# imu_3_yz.net
KiCad netlist of a schematic drawn in EAGLE
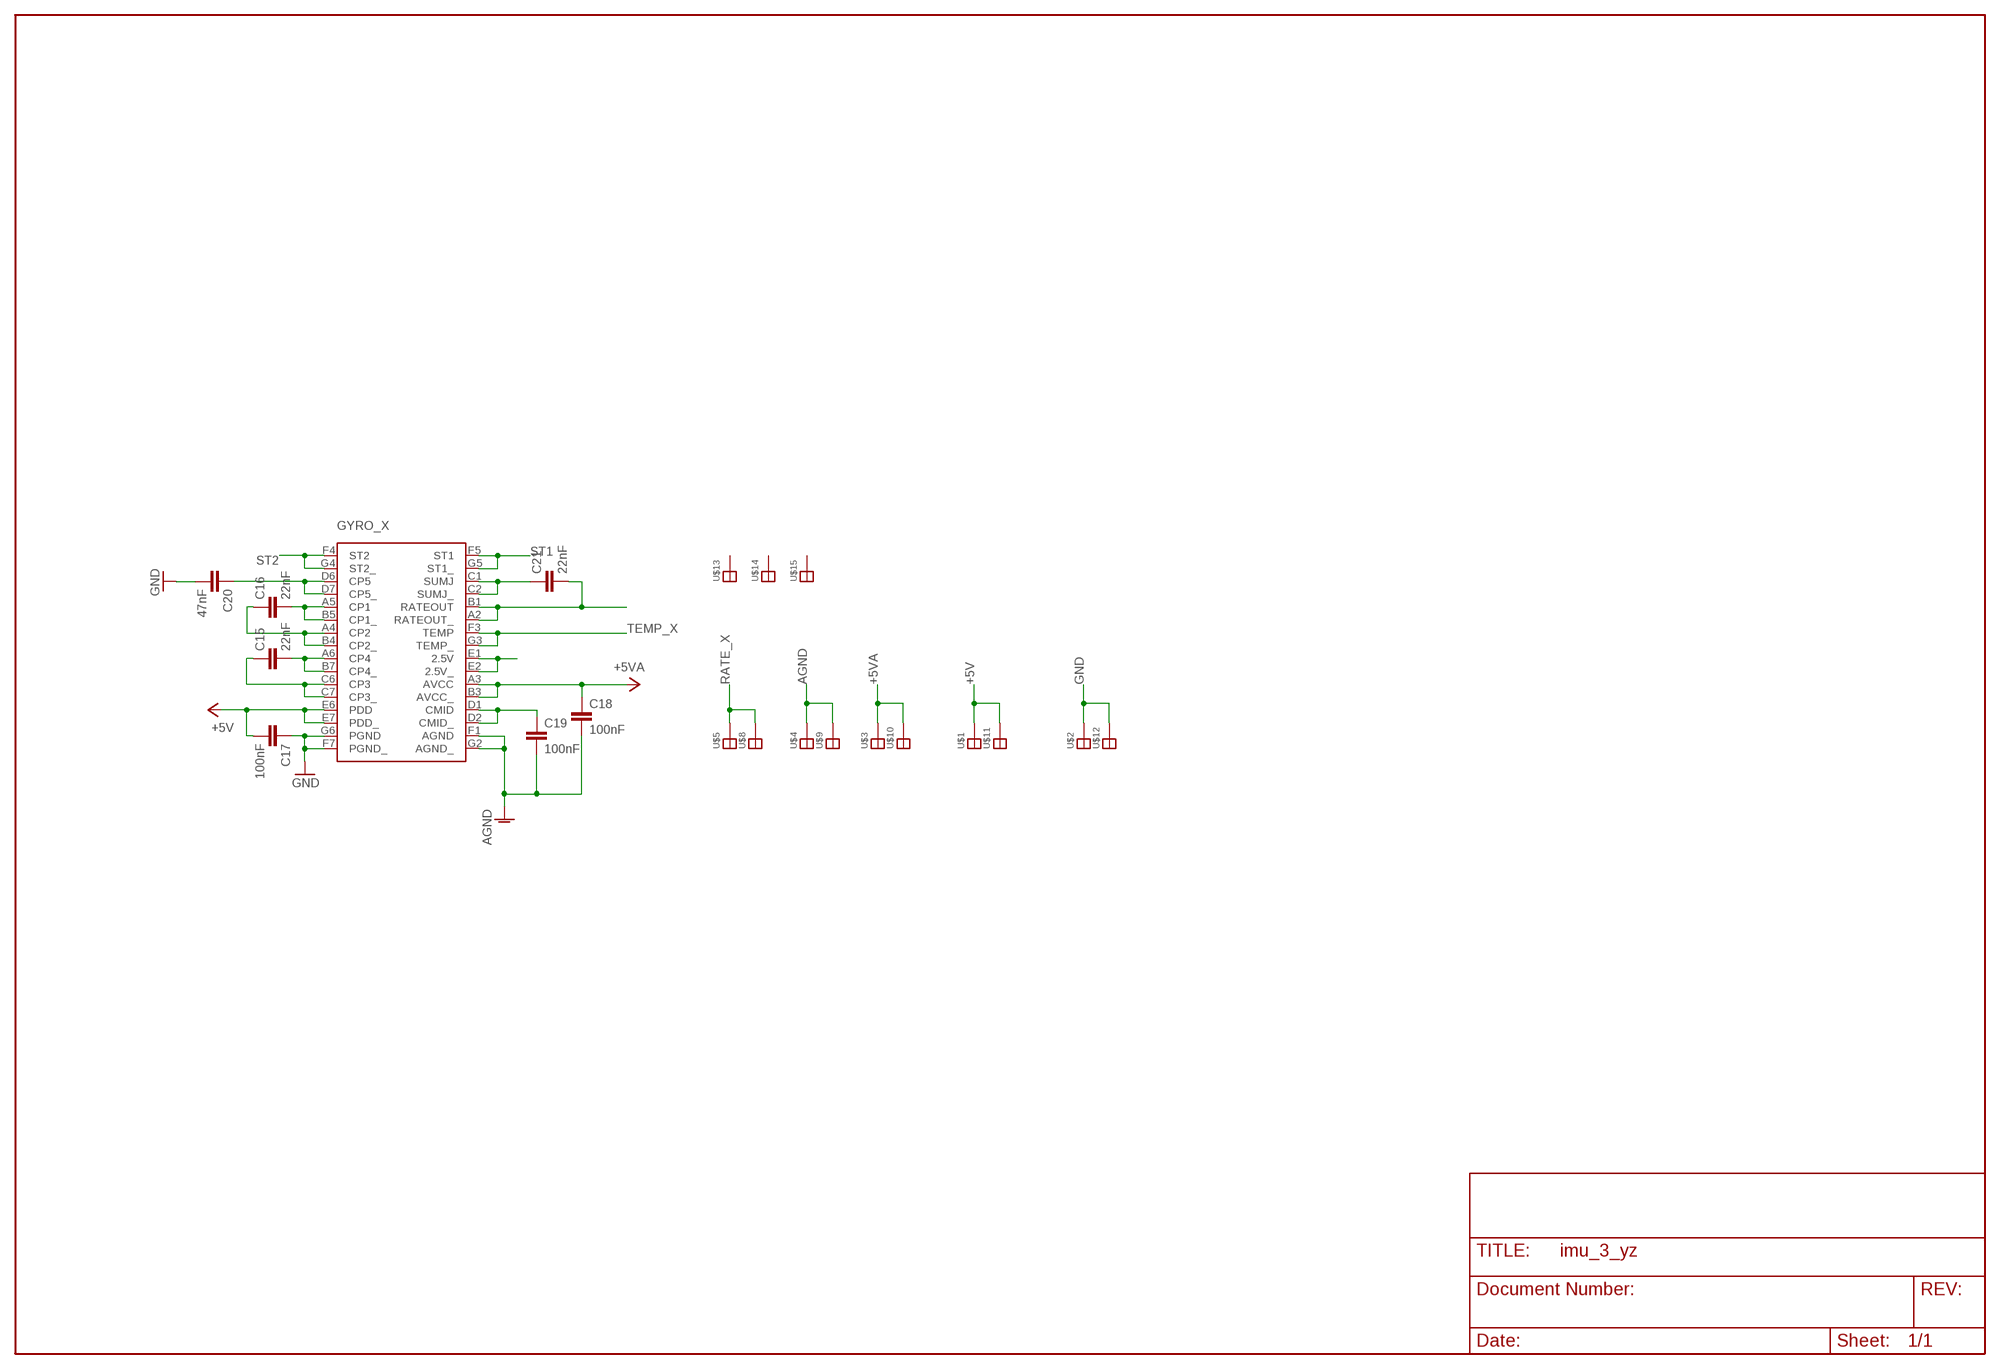
[diagram p0: schematic, sheet 1]

(export (version "E")
  (design (tool "Eeschema 10.0.6"))
  (components
    (comp (ref "C15")
      (value "22nF")
      (footprint "eagle-import:C0402K")
      (libsource (lib "eagle-import") (part "C-EUC0402K"))
    )
    (comp (ref "C16")
      (value "22nF")
      (footprint "eagle-import:C0402K")
      (libsource (lib "eagle-import") (part "C-EUC0402K"))
    )
    (comp (ref "C17")
      (value "100nF")
      (footprint "eagle-import:C0402K")
      (libsource (lib "eagle-import") (part "C-EUC0402K"))
    )
    (comp (ref "C18")
      (value "100nF")
      (footprint "eagle-import:C0402K")
      (libsource (lib "eagle-import") (part "C-EUC0402K"))
    )
    (comp (ref "C19")
      (value "100nF")
      (footprint "eagle-import:C0402K")
      (libsource (lib "eagle-import") (part "C-EUC0402K"))
    )
    (comp (ref "C20")
      (value "47nF")
      (footprint "eagle-import:C0402K")
      (libsource (lib "eagle-import") (part "C-EUC0402K"))
    )
    (comp (ref "C21")
      (value "22nF")
      (footprint "eagle-import:C0402K")
      (libsource (lib "eagle-import") (part "C-EUC0402K"))
    )
    (comp (ref "GYRO_X")
      (value "ADXR")
      (footprint "eagle-import:BC-32")
      (libsource (lib "eagle-import") (part "ADXR"))
    )
    (comp (ref "U$1")
      (value "SOLDER_PAD")
      (footprint "eagle-import:SOLDER_PAD")
      (libsource (lib "eagle-import") (part "SOLDER_PAD"))
    )
    (comp (ref "U$2")
      (value "SOLDER_PAD")
      (footprint "eagle-import:SOLDER_PAD")
      (libsource (lib "eagle-import") (part "SOLDER_PAD"))
    )
    (comp (ref "U$3")
      (value "SOLDER_PAD")
      (footprint "eagle-import:SOLDER_PAD")
      (libsource (lib "eagle-import") (part "SOLDER_PAD"))
    )
    (comp (ref "U$4")
      (value "SOLDER_PAD")
      (footprint "eagle-import:SOLDER_PAD")
      (libsource (lib "eagle-import") (part "SOLDER_PAD"))
    )
    (comp (ref "U$5")
      (value "SOLDER_PAD")
      (footprint "eagle-import:SOLDER_PAD")
      (libsource (lib "eagle-import") (part "SOLDER_PAD"))
    )
    (comp (ref "U$8")
      (value "SOLDER_PAD")
      (footprint "eagle-import:SOLDER_PAD")
      (libsource (lib "eagle-import") (part "SOLDER_PAD"))
    )
    (comp (ref "U$9")
      (value "SOLDER_PAD")
      (footprint "eagle-import:SOLDER_PAD")
      (libsource (lib "eagle-import") (part "SOLDER_PAD"))
    )
    (comp (ref "U$10")
      (value "SOLDER_PAD")
      (footprint "eagle-import:SOLDER_PAD")
      (libsource (lib "eagle-import") (part "SOLDER_PAD"))
    )
    (comp (ref "U$11")
      (value "SOLDER_PAD")
      (footprint "eagle-import:SOLDER_PAD")
      (libsource (lib "eagle-import") (part "SOLDER_PAD"))
    )
    (comp (ref "U$12")
      (value "SOLDER_PAD")
      (footprint "eagle-import:SOLDER_PAD")
      (libsource (lib "eagle-import") (part "SOLDER_PAD"))
    )
    (comp (ref "U$13")
      (value "SOLDER_PAD")
      (footprint "eagle-import:SOLDER_PAD")
      (libsource (lib "eagle-import") (part "SOLDER_PAD"))
    )
    (comp (ref "U$14")
      (value "SOLDER_PAD")
      (footprint "eagle-import:SOLDER_PAD")
      (libsource (lib "eagle-import") (part "SOLDER_PAD"))
    )
    (comp (ref "U$15")
      (value "SOLDER_PAD")
      (footprint "eagle-import:SOLDER_PAD")
      (libsource (lib "eagle-import") (part "SOLDER_PAD"))
    )
  )
  (nets
    (net (code "1") (name "+5V") (class "Default")
      (node (ref "C17") (pin "2") (pinfunction "2_2") (pintype "passive"))
      (node (ref "GYRO_X") (pin "E6") (pinfunction "PDD_E6") (pintype "bidirectional"))
      (node (ref "GYRO_X") (pin "E7") (pinfunction "PDD__E7") (pintype "bidirectional"))
      (node (ref "U$1") (pin "P$1") (pinfunction "P$1_P$1") (pintype "bidirectional"))
      (node (ref "U$11") (pin "P$1") (pinfunction "P$1_P$1") (pintype "bidirectional"))
    )
    (net (code "2") (name "+5VA") (class "Default")
      (node (ref "C18") (pin "1") (pinfunction "1_1") (pintype "passive"))
      (node (ref "GYRO_X") (pin "A3") (pinfunction "AVCC_A3") (pintype "bidirectional"))
      (node (ref "GYRO_X") (pin "B3") (pinfunction "AVCC__B3") (pintype "bidirectional"))
      (node (ref "U$10") (pin "P$1") (pinfunction "P$1_P$1") (pintype "bidirectional"))
      (node (ref "U$3") (pin "P$1") (pinfunction "P$1_P$1") (pintype "bidirectional"))
    )
    (net (code "3") (name "/RATE_X") (class "Default")
      (node (ref "C21") (pin "2") (pinfunction "2_2") (pintype "passive"))
      (node (ref "GYRO_X") (pin "A2") (pinfunction "RATEOUT__A2") (pintype "bidirectional"))
      (node (ref "GYRO_X") (pin "B1") (pinfunction "RATEOUT_B1") (pintype "bidirectional"))
      (node (ref "U$5") (pin "P$1") (pinfunction "P$1_P$1") (pintype "bidirectional"))
      (node (ref "U$8") (pin "P$1") (pinfunction "P$1_P$1") (pintype "bidirectional"))
    )
    (net (code "4") (name "/ST1") (class "Default")
      (node (ref "GYRO_X") (pin "F5") (pinfunction "ST1_F5") (pintype "bidirectional"))
      (node (ref "GYRO_X") (pin "G5") (pinfunction "ST1__G5") (pintype "bidirectional"))
    )
    (net (code "5") (name "/ST2") (class "Default")
      (node (ref "GYRO_X") (pin "F4") (pinfunction "ST2_F4") (pintype "bidirectional"))
      (node (ref "GYRO_X") (pin "G4") (pinfunction "ST2__G4") (pintype "bidirectional"))
    )
    (net (code "6") (name "/TEMP_X") (class "Default")
      (node (ref "GYRO_X") (pin "F3") (pinfunction "TEMP_F3") (pintype "bidirectional"))
      (node (ref "GYRO_X") (pin "G3") (pinfunction "TEMP__G3") (pintype "bidirectional"))
    )
    (net (code "7") (name "AGND") (class "Default")
      (node (ref "C18") (pin "2") (pinfunction "2_2") (pintype "passive"))
      (node (ref "C19") (pin "2") (pinfunction "2_2") (pintype "passive"))
      (node (ref "GYRO_X") (pin "F1") (pinfunction "AGND_F1") (pintype "bidirectional"))
      (node (ref "GYRO_X") (pin "G2") (pinfunction "AGND__G2") (pintype "bidirectional"))
      (node (ref "U$4") (pin "P$1") (pinfunction "P$1_P$1") (pintype "bidirectional"))
      (node (ref "U$9") (pin "P$1") (pinfunction "P$1_P$1") (pintype "bidirectional"))
    )
    (net (code "8") (name "GND") (class "Default")
      (node (ref "C17") (pin "1") (pinfunction "1_1") (pintype "passive"))
      (node (ref "C20") (pin "2") (pinfunction "2_2") (pintype "passive"))
      (node (ref "GYRO_X") (pin "F7") (pinfunction "PGND__F7") (pintype "bidirectional"))
      (node (ref "GYRO_X") (pin "G6") (pinfunction "PGND_G6") (pintype "bidirectional"))
      (node (ref "U$12") (pin "P$1") (pinfunction "P$1_P$1") (pintype "bidirectional"))
      (node (ref "U$2") (pin "P$1") (pinfunction "P$1_P$1") (pintype "bidirectional"))
    )
    (net (code "9") (name "Net-(GYRO_X-2.5V)") (class "Default")
      (node (ref "GYRO_X") (pin "E1") (pinfunction "2.5V_E1") (pintype "bidirectional"))
      (node (ref "GYRO_X") (pin "E2") (pinfunction "2.5V__E2") (pintype "bidirectional"))
    )
    (net (code "10") (name "Net-(GYRO_X-CMID)") (class "Default")
      (node (ref "C19") (pin "1") (pinfunction "1_1") (pintype "passive"))
      (node (ref "GYRO_X") (pin "D1") (pinfunction "CMID_D1") (pintype "bidirectional"))
      (node (ref "GYRO_X") (pin "D2") (pinfunction "CMID__D2") (pintype "bidirectional"))
    )
    (net (code "11") (name "Net-(GYRO_X-CP1)") (class "Default")
      (node (ref "C16") (pin "2") (pinfunction "2_2") (pintype "passive"))
      (node (ref "GYRO_X") (pin "A5") (pinfunction "CP1_A5") (pintype "bidirectional"))
      (node (ref "GYRO_X") (pin "B5") (pinfunction "CP1__B5") (pintype "bidirectional"))
    )
    (net (code "12") (name "Net-(GYRO_X-CP2)") (class "Default")
      (node (ref "C16") (pin "1") (pinfunction "1_1") (pintype "passive"))
      (node (ref "GYRO_X") (pin "A4") (pinfunction "CP2_A4") (pintype "bidirectional"))
      (node (ref "GYRO_X") (pin "B4") (pinfunction "CP2__B4") (pintype "bidirectional"))
    )
    (net (code "13") (name "Net-(GYRO_X-CP3)") (class "Default")
      (node (ref "C15") (pin "1") (pinfunction "1_1") (pintype "passive"))
      (node (ref "GYRO_X") (pin "C6") (pinfunction "CP3_C6") (pintype "bidirectional"))
      (node (ref "GYRO_X") (pin "C7") (pinfunction "CP3__C7") (pintype "bidirectional"))
    )
    (net (code "14") (name "Net-(GYRO_X-CP4)") (class "Default")
      (node (ref "C15") (pin "2") (pinfunction "2_2") (pintype "passive"))
      (node (ref "GYRO_X") (pin "A6") (pinfunction "CP4_A6") (pintype "bidirectional"))
      (node (ref "GYRO_X") (pin "B7") (pinfunction "CP4__B7") (pintype "bidirectional"))
    )
    (net (code "15") (name "Net-(GYRO_X-CP5)") (class "Default")
      (node (ref "C20") (pin "1") (pinfunction "1_1") (pintype "passive"))
      (node (ref "GYRO_X") (pin "D6") (pinfunction "CP5_D6") (pintype "bidirectional"))
      (node (ref "GYRO_X") (pin "D7") (pinfunction "CP5__D7") (pintype "bidirectional"))
    )
    (net (code "16") (name "Net-(GYRO_X-SUMJ)") (class "Default")
      (node (ref "C21") (pin "1") (pinfunction "1_1") (pintype "passive"))
      (node (ref "GYRO_X") (pin "C1") (pinfunction "SUMJ_C1") (pintype "bidirectional"))
      (node (ref "GYRO_X") (pin "C2") (pinfunction "SUMJ__C2") (pintype "bidirectional"))
    )
    (net (code "17") (name "unconnected-(U$13-PadP$1)") (class "Default")
      (node (ref "U$13") (pin "P$1") (pinfunction "P$1_P$1") (pintype "bidirectional"))
    )
    (net (code "18") (name "unconnected-(U$14-PadP$1)") (class "Default")
      (node (ref "U$14") (pin "P$1") (pinfunction "P$1_P$1") (pintype "bidirectional"))
    )
    (net (code "19") (name "unconnected-(U$15-PadP$1)") (class "Default")
      (node (ref "U$15") (pin "P$1") (pinfunction "P$1_P$1") (pintype "bidirectional"))
    )
  )
)
